# RawrRacing_EngineKillSwitch.net
KiCad netlist of a schematic drawn in EAGLE
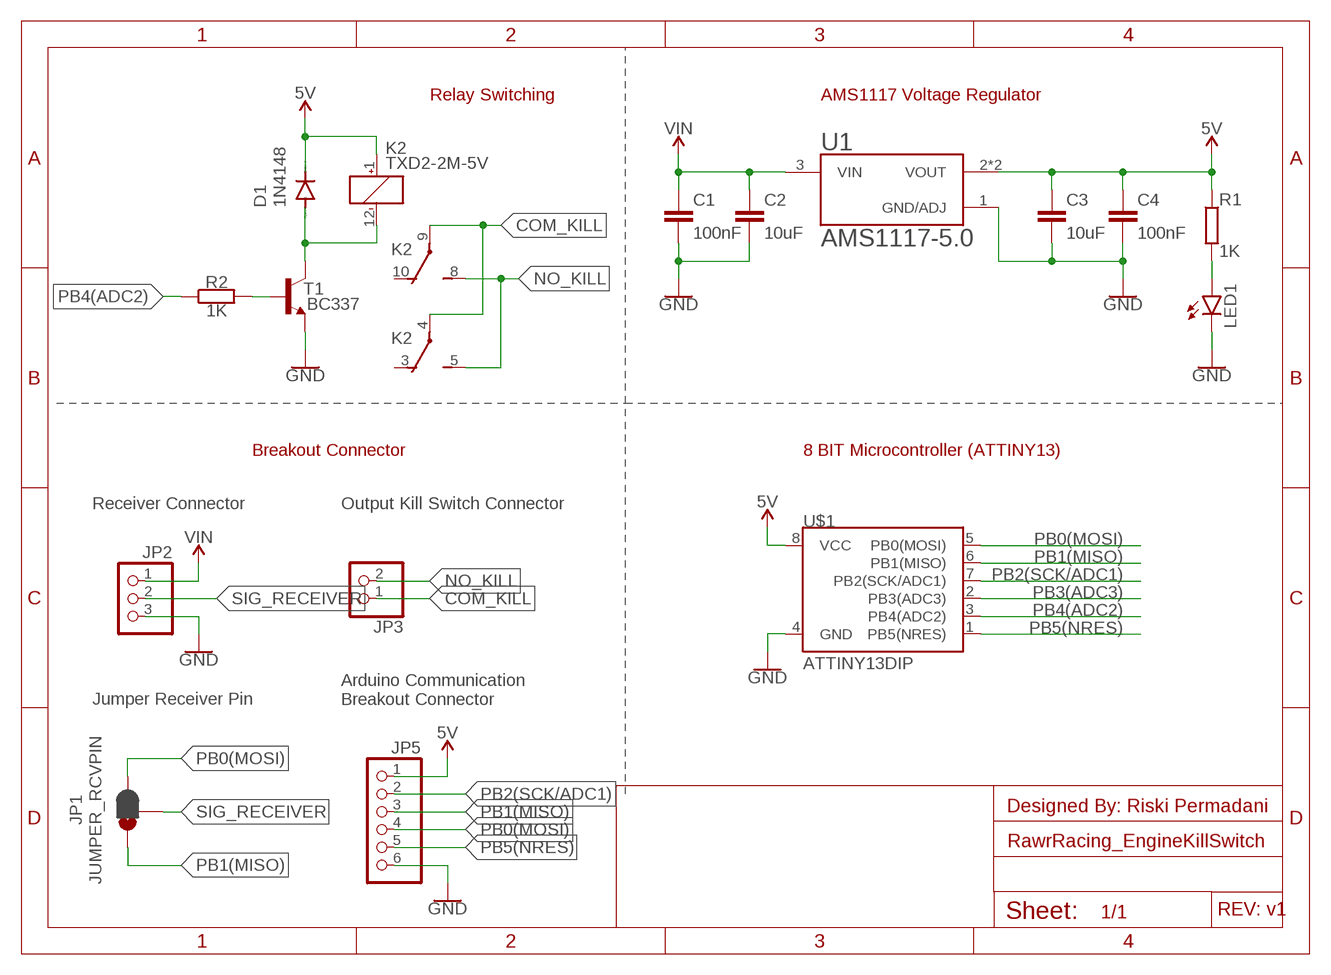
[diagram p0: schematic, sheet 1]

(export (version "E")
  (design (tool "Eeschema 10.0.6"))
  (components
    (comp (ref "C1")
      (value "100nF")
      (footprint "eagle-import:C0603")
      (libsource (lib "eagle-import") (part "C-EUC0603"))
    )
    (comp (ref "C2")
      (value "10uF")
      (footprint "eagle-import:C0603")
      (libsource (lib "eagle-import") (part "C-EUC0603"))
    )
    (comp (ref "C3")
      (value "10uF")
      (footprint "eagle-import:C0603")
      (libsource (lib "eagle-import") (part "C-EUC0603"))
    )
    (comp (ref "C4")
      (value "100nF")
      (footprint "eagle-import:C0603")
      (libsource (lib "eagle-import") (part "C-EUC0603"))
    )
    (comp (ref "D1")
      (value "1N4148")
      (footprint "eagle-import:SOD80C")
      (libsource (lib "eagle-import") (part "DIODE-SOD80C"))
    )
    (comp (ref "JP1")
      (value "JUMPER_RCVPIN")
      (footprint "eagle-import:SMT-JUMPER_3_1-NC_PASTE_SILK")
      (libsource (lib "eagle-import") (part "JUMPER-SMT_3_1-NC_PASTE_SILK"))
    )
    (comp (ref "JP2")
      (value "PINHD-1X3/90")
      (footprint "eagle-import:1X03_90")
      (libsource (lib "eagle-import") (part "PINHD-1X3/90"))
    )
    (comp (ref "JP3")
      (value "PINHD-1X2/90")
      (footprint "eagle-import:1X02_90")
      (libsource (lib "eagle-import") (part "PINHD-1X2/90"))
    )
    (comp (ref "JP5")
      (value "PINHD-1X6")
      (footprint "eagle-import:1X06")
      (libsource (lib "eagle-import") (part "PINHD-1X6"))
    )
    (comp (ref "K2")
      (value "TXD2-2M-5V")
      (footprint "eagle-import:TXD2")
      (libsource (lib "eagle-import") (part "TX?-D2-2M5V"))
    )
    (comp (ref "LED1")
      (value "LEDSML0603")
      (footprint "eagle-import:SML0603")
      (libsource (lib "eagle-import") (part "LEDSML0603"))
    )
    (comp (ref "R1")
      (value "1K")
      (footprint "eagle-import:R0603")
      (libsource (lib "eagle-import") (part "R-EU_R0603"))
    )
    (comp (ref "R2")
      (value "1K")
      (footprint "eagle-import:R0603")
      (libsource (lib "eagle-import") (part "R-EU_R0603"))
    )
    (comp (ref "T1")
      (value "BC337")
      (footprint "eagle-import:TO92")
      (libsource (lib "eagle-import") (part "BC337"))
    )
    (comp (ref "U$1")
      (value "ATTINY13DIP")
      (footprint "eagle-import:DIP08_MCU")
      (libsource (lib "eagle-import") (part "ATTINY13DIP"))
    )
    (comp (ref "U1")
      (value "AMS1117-5.0")
      (footprint "eagle-import:SOT229P700X180-4N")
      (fields (field (name "MF") "Advanced Monolithic Systems"))
      (libsource (lib "eagle-import") (part "AMS1117-5.0"))
    )
  )
  (nets
    (net (code "1") (name "/PB3(ADC3)") (class "Default")
      (node (ref "U$1") (pin "2") (pinfunction "PB3(ADC3)_2") (pintype "bidirectional"))
    )
    (net (code "2") (name "5V") (class "Default")
      (node (ref "C3") (pin "1") (pinfunction "1_1") (pintype "passive"))
      (node (ref "C4") (pin "1") (pinfunction "1_1") (pintype "passive"))
      (node (ref "D1") (pin "C") (pinfunction "C_C") (pintype "passive"))
      (node (ref "JP5") (pin "1") (pinfunction "1_1") (pintype "passive"))
      (node (ref "K2") (pin "1") (pinfunction "+_1") (pintype "passive"))
      (node (ref "R1") (pin "1") (pinfunction "1_1") (pintype "passive"))
      (node (ref "U$1") (pin "8") (pinfunction "VCC_8") (pintype "bidirectional"))
      (node (ref "U1") (pin "2") (pinfunction "VOUT_2") (pintype "output"))
      (node (ref "U1") (pin "4") (pinfunction "VOUT_4") (pintype "output"))
    )
    (net (code "3") (name "COM_KILL") (class "Default")
      (node (ref "JP3") (pin "1") (pinfunction "1_1") (pintype "passive"))
      (node (ref "K2") (pin "4") (pinfunction "P_4") (pintype "passive"))
      (node (ref "K2") (pin "9") (pinfunction "P_9") (pintype "passive"))
    )
    (net (code "4") (name "GND") (class "Default")
      (node (ref "C1") (pin "2") (pinfunction "2_2") (pintype "passive"))
      (node (ref "C2") (pin "2") (pinfunction "2_2") (pintype "passive"))
      (node (ref "C3") (pin "2") (pinfunction "2_2") (pintype "passive"))
      (node (ref "C4") (pin "2") (pinfunction "2_2") (pintype "passive"))
      (node (ref "JP2") (pin "3") (pinfunction "3_3") (pintype "passive"))
      (node (ref "JP5") (pin "6") (pinfunction "6_6") (pintype "passive"))
      (node (ref "LED1") (pin "C") (pinfunction "C_C") (pintype "passive"))
      (node (ref "T1") (pin "1") (pinfunction "E_1") (pintype "passive"))
      (node (ref "U$1") (pin "4") (pinfunction "GND_4") (pintype "bidirectional"))
      (node (ref "U1") (pin "1") (pinfunction "GND/ADJ_1") (pintype "power_in"))
    )
    (net (code "5") (name "NO_KILL") (class "Default")
      (node (ref "JP3") (pin "2") (pinfunction "2_2") (pintype "passive"))
      (node (ref "K2") (pin "5") (pinfunction "S_5") (pintype "passive"))
      (node (ref "K2") (pin "8") (pinfunction "S_8") (pintype "passive"))
    )
    (net (code "6") (name "Net-(K2C--)") (class "Default")
      (node (ref "D1") (pin "A") (pinfunction "A_A") (pintype "passive"))
      (node (ref "K2") (pin "12") (pinfunction "-_12") (pintype "passive"))
      (node (ref "T1") (pin "3") (pinfunction "C_3") (pintype "passive"))
    )
    (net (code "7") (name "Net-(LED1-PadA)") (class "Default")
      (node (ref "LED1") (pin "A") (pinfunction "A_A") (pintype "passive"))
      (node (ref "R1") (pin "2") (pinfunction "2_2") (pintype "passive"))
    )
    (net (code "8") (name "Net-(T1-B)") (class "Default")
      (node (ref "R2") (pin "2") (pinfunction "2_2") (pintype "passive"))
      (node (ref "T1") (pin "2") (pinfunction "B_2") (pintype "passive"))
    )
    (net (code "9") (name "PB0(MOSI)") (class "Default")
      (node (ref "JP1") (pin "3") (pinfunction "3_3") (pintype "passive"))
      (node (ref "JP5") (pin "4") (pinfunction "4_4") (pintype "passive"))
      (node (ref "U$1") (pin "5") (pinfunction "PB0(MOSI)_5") (pintype "bidirectional"))
    )
    (net (code "10") (name "PB1(MISO)") (class "Default")
      (node (ref "JP1") (pin "1") (pinfunction "1_1") (pintype "passive"))
      (node (ref "JP5") (pin "3") (pinfunction "3_3") (pintype "passive"))
      (node (ref "U$1") (pin "6") (pinfunction "PB1(MISO)_6") (pintype "bidirectional"))
    )
    (net (code "11") (name "PB2(SCK{slash}ADC1)") (class "Default")
      (node (ref "JP5") (pin "2") (pinfunction "2_2") (pintype "passive"))
      (node (ref "U$1") (pin "7") (pinfunction "PB2(SCK/ADC1)_7") (pintype "bidirectional"))
    )
    (net (code "12") (name "PB4(ADC2)") (class "Default")
      (node (ref "R2") (pin "1") (pinfunction "1_1") (pintype "passive"))
      (node (ref "U$1") (pin "3") (pinfunction "PB4(ADC2)_3") (pintype "bidirectional"))
    )
    (net (code "13") (name "PB5(NRES)") (class "Default")
      (node (ref "JP5") (pin "5") (pinfunction "5_5") (pintype "passive"))
      (node (ref "U$1") (pin "1") (pinfunction "PB5(NRES)_1") (pintype "bidirectional"))
    )
    (net (code "14") (name "SIG_RECEIVER") (class "Default")
      (node (ref "JP1") (pin "2") (pinfunction "2_2") (pintype "passive"))
      (node (ref "JP2") (pin "2") (pinfunction "2_2") (pintype "passive"))
    )
    (net (code "15") (name "VIN") (class "Default")
      (node (ref "C1") (pin "1") (pinfunction "1_1") (pintype "passive"))
      (node (ref "C2") (pin "1") (pinfunction "1_1") (pintype "passive"))
      (node (ref "JP2") (pin "1") (pinfunction "1_1") (pintype "passive"))
      (node (ref "U1") (pin "3") (pinfunction "VIN_3") (pintype "input"))
    )
    (net (code "16") (name "unconnected-(K2A-O-Pad3)") (class "Default")
      (node (ref "K2") (pin "3") (pinfunction "O_3") (pintype "passive"))
    )
    (net (code "17") (name "unconnected-(K2B-O-Pad10)") (class "Default")
      (node (ref "K2") (pin "10") (pinfunction "O_10") (pintype "passive"))
    )
  )
)
